# 01-POWER.net
KiCad netlist of a schematic drawn in Altium Designer
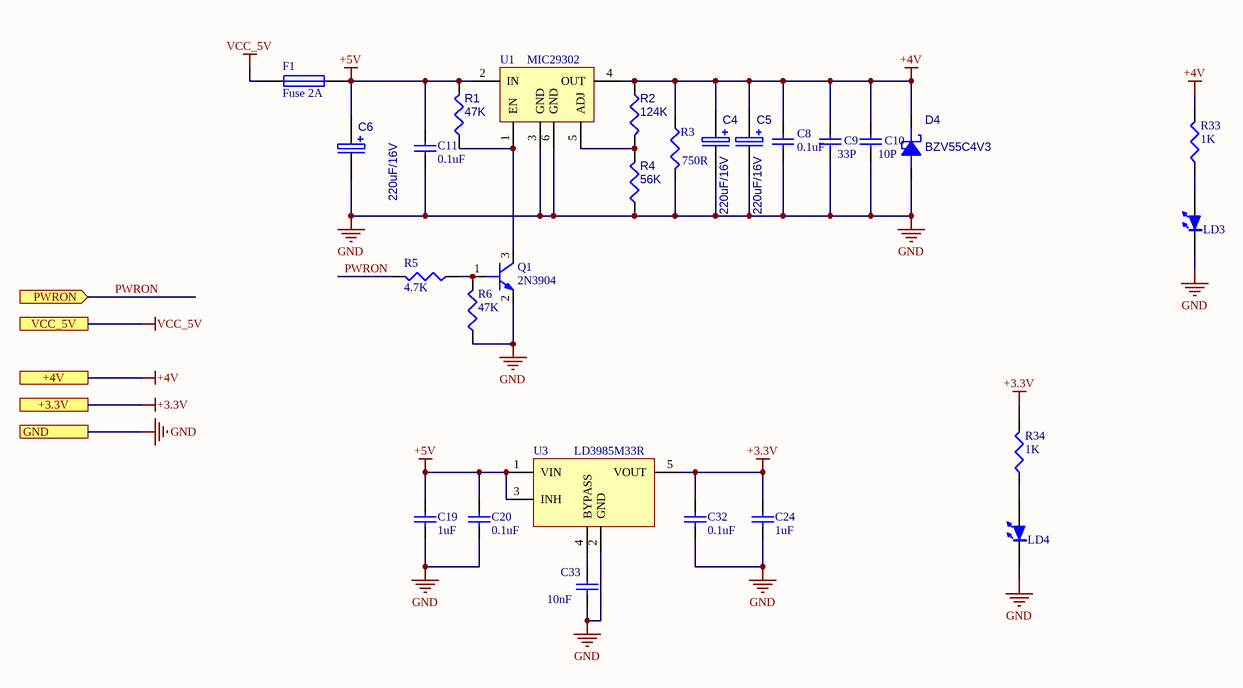
[diagram p0: 01-POWER.SchDoc]

(export (version "E")
  (design (tool "Eeschema 10.0.6"))
  (components
    (comp (ref "C4")
      (value "220uF/16V")
      (footprint "C_TAN_D")
      (description "E-CAP")
      (libsource (lib "*") (part "ECAP"))
    )
    (comp (ref "C5")
      (value "220uF/16V")
      (footprint "C_TAN_D")
      (description "E-CAP")
      (libsource (lib "*") (part "ECAP"))
    )
    (comp (ref "C6")
      (value "220uF/16V")
      (footprint "C_TAN_D")
      (description "E-CAP")
      (libsource (lib "*") (part "ECAP"))
    )
    (comp (ref "C8")
      (value "0.1uF")
      (footprint "0603_C")
      (description "Capacitor")
      (fields (field (name "PUBLISHER") "Altium Limited"))
      (libsource (lib "EP_MCB_V3.00") (part "Cap Semi"))
    )
    (comp (ref "C9")
      (value "33P")
      (footprint "0603_C")
      (description "Capacitor")
      (fields (field (name "PUBLISHER") "Altium Limited"))
      (libsource (lib "EP_MCB_V3.00") (part "Cap Semi"))
    )
    (comp (ref "C10")
      (value "10P")
      (footprint "0603_C")
      (description "Capacitor")
      (fields (field (name "PUBLISHER") "Altium Limited"))
      (libsource (lib "EP_MCB_V3.00") (part "Cap Semi"))
    )
    (comp (ref "C11")
      (value "0.1uF")
      (footprint "0603_C")
      (description "Capacitor")
      (fields (field (name "PUBLISHER") "Altium Limited"))
      (libsource (lib "EP_MCB_V3.00") (part "Cap Semi"))
    )
    (comp (ref "C19")
      (value "1uF")
      (footprint "0603_C")
      (description "Capacitor")
      (fields (field (name "PUBLISHER") "Altium Limited"))
      (libsource (lib "EM_SENSOR_V3.01") (part "Cap Semi_1"))
    )
    (comp (ref "C20")
      (value "0.1uF")
      (footprint "0603_C")
      (description "Capacitor")
      (fields (field (name "PUBLISHER") "Altium Limited"))
      (libsource (lib "EM_SENSOR_V3.01") (part "Cap Semi_1"))
    )
    (comp (ref "C24")
      (value "1uF")
      (footprint "0603_C")
      (description "Capacitor")
      (fields (field (name "PUBLISHER") "Altium Limited"))
      (libsource (lib "EM_SENSOR_V3.01") (part "Cap Semi_1"))
    )
    (comp (ref "C32")
      (value "0.1uF")
      (footprint "0603_C")
      (description "Capacitor")
      (fields (field (name "PUBLISHER") "Altium Limited"))
      (libsource (lib "EM_SENSOR_V3.01") (part "Cap Semi_1"))
    )
    (comp (ref "C33")
      (value "10nF")
      (footprint "0603_C")
      (description "Capacitor")
      (fields (field (name "PUBLISHER") "Altium Limited"))
      (libsource (lib "EM_SENSOR_V3.01") (part "Cap Semi_1"))
    )
    (comp (ref "D4")
      (value "BZV55C4V3")
      (footprint "SOD-80")
      (libsource (lib "EP_MCB_V4.1") (part "DIODE SCHOTTKY"))
    )
    (comp (ref "F1")
      (value "Fuse 2A")
      (footprint "1812_F")
      (description "Fuse")
      (fields (field (name "PUBLISHER") "Altium Limited"))
      (libsource (lib "Miscellaneous Devices") (part "Fuse 1"))
    )
    (comp (ref "LD3")
      (value "WHITE")
      (footprint "LED_0603")
      (description "LED")
      (libsource (lib "*") (part "LED"))
    )
    (comp (ref "LD4")
      (value "WHITE")
      (footprint "LED_0603")
      (description "LED")
      (libsource (lib "*") (part "LED"))
    )
    (comp (ref "Q1") (value "2N3904") (footprint "SOT23") (libsource (lib "MySchlib") (part "NPN")))
    (comp (ref "R1")
      (value "47K")
      (footprint "0603_R")
      (description "RESISTOR")
      (libsource (lib "*") (part "R0.25W"))
    )
    (comp (ref "R2")
      (value "124K")
      (footprint "0603_R")
      (description "RESISTOR")
      (libsource (lib "*") (part "R0.25W"))
    )
    (comp (ref "R3") (value "750R") (footprint "0603_R") (libsource (lib "") (part "RES1_1")))
    (comp (ref "R4")
      (value "56K")
      (footprint "0603_R")
      (description "RESISTOR")
      (libsource (lib "*") (part "R0.25W"))
    )
    (comp (ref "R5") (value "4.7K") (footprint "0603_R") (libsource (lib "MySchlib") (part "RES1")))
    (comp (ref "R6") (value "47K") (footprint "0603_R") (libsource (lib "MySchlib") (part "RES1")))
    (comp (ref "R33") (value "1K") (footprint "0603_R") (libsource (lib "MySchlib") (part "RES1")))
    (comp (ref "R34") (value "1K") (footprint "0603_R") (libsource (lib "MySchlib") (part "RES1")))
    (comp (ref "U1") (value "MIC29302") (footprint "TO-263-5") (libsource (lib "MySchlib") (part "MIC29302")))
    (comp (ref "U3")
      (value "LD3985M33R")
      (footprint "SOT23-5L")
      (libsource (lib "MySchlib") (part "LD3985MSSR"))
    )
  )
  (nets
    (net (code "1") (name "+3.3V") (class "Default")
      (node (ref "C24") (pin "1") (pinfunction "1_1") (pintype "passive"))
      (node (ref "C32") (pin "1") (pinfunction "1_1") (pintype "passive"))
      (node (ref "R34") (pin "1") (pinfunction "1_1") (pintype "passive"))
      (node (ref "U3") (pin "5") (pinfunction "VOUT_5") (pintype "passive"))
    )
    (net (code "2") (name "+4V") (class "Default")
      (node (ref "C10") (pin "2") (pinfunction "2_2") (pintype "passive"))
      (node (ref "C4") (pin "1") (pinfunction "+_1") (pintype "passive"))
      (node (ref "C5") (pin "1") (pinfunction "+_1") (pintype "passive"))
      (node (ref "C8") (pin "2") (pinfunction "2_2") (pintype "passive"))
      (node (ref "C9") (pin "2") (pinfunction "2_2") (pintype "passive"))
      (node (ref "D4") (pin "2") (pinfunction "CATHODE_2") (pintype "passive"))
      (node (ref "R2") (pin "2") (pinfunction "2_2") (pintype "passive"))
      (node (ref "R3") (pin "2") (pinfunction "2_2") (pintype "passive"))
      (node (ref "R33") (pin "1") (pinfunction "1_1") (pintype "passive"))
      (node (ref "U1") (pin "4") (pinfunction "OUT_4") (pintype "passive"))
    )
    (net (code "3") (name "+5V") (class "Default")
      (node (ref "C11") (pin "2") (pinfunction "2_2") (pintype "passive"))
      (node (ref "C19") (pin "1") (pinfunction "1_1") (pintype "passive"))
      (node (ref "C20") (pin "1") (pinfunction "1_1") (pintype "passive"))
      (node (ref "C6") (pin "1") (pinfunction "+_1") (pintype "passive"))
      (node (ref "F1") (pin "2") (pinfunction "2_2") (pintype "passive"))
      (node (ref "R1") (pin "1") (pinfunction "1_1") (pintype "passive"))
      (node (ref "U1") (pin "2") (pinfunction "IN_2") (pintype "passive"))
      (node (ref "U3") (pin "1") (pinfunction "VIN_1") (pintype "passive"))
      (node (ref "U3") (pin "3") (pinfunction "INH_3") (pintype "passive"))
    )
    (net (code "4") (name "/PWRON") (class "Default")
      (node (ref "R5") (pin "1") (pinfunction "1_1") (pintype "passive"))
    )
    (net (code "5") (name "GND") (class "Default")
      (node (ref "C10") (pin "1") (pinfunction "1_1") (pintype "passive"))
      (node (ref "C11") (pin "1") (pinfunction "1_1") (pintype "passive"))
      (node (ref "C19") (pin "2") (pinfunction "2_2") (pintype "passive"))
      (node (ref "C20") (pin "2") (pinfunction "2_2") (pintype "passive"))
      (node (ref "C24") (pin "2") (pinfunction "2_2") (pintype "passive"))
      (node (ref "C32") (pin "2") (pinfunction "2_2") (pintype "passive"))
      (node (ref "C33") (pin "2") (pinfunction "2_2") (pintype "passive"))
      (node (ref "C4") (pin "2") (pinfunction "-_2") (pintype "passive"))
      (node (ref "C5") (pin "2") (pinfunction "-_2") (pintype "passive"))
      (node (ref "C6") (pin "2") (pinfunction "-_2") (pintype "passive"))
      (node (ref "C8") (pin "1") (pinfunction "1_1") (pintype "passive"))
      (node (ref "C9") (pin "1") (pinfunction "1_1") (pintype "passive"))
      (node (ref "D4") (pin "1") (pinfunction "ANODE_1") (pintype "passive"))
      (node (ref "LD3") (pin "K") (pinfunction "K_K") (pintype "passive"))
      (node (ref "LD4") (pin "K") (pinfunction "K_K") (pintype "passive"))
      (node (ref "Q1") (pin "2") (pinfunction "EMITTER_2") (pintype "passive"))
      (node (ref "R3") (pin "1") (pinfunction "1_1") (pintype "passive"))
      (node (ref "R4") (pin "2") (pinfunction "2_2") (pintype "passive"))
      (node (ref "R6") (pin "2") (pinfunction "2_2") (pintype "passive"))
      (node (ref "U1") (pin "3") (pinfunction "GND_3") (pintype "passive"))
      (node (ref "U1") (pin "6") (pinfunction "GND_6") (pintype "passive"))
      (node (ref "U3") (pin "2") (pinfunction "GND_2") (pintype "passive"))
    )
    (net (code "6") (name "Net-(LD3-PadA)") (class "Default")
      (node (ref "LD3") (pin "A") (pinfunction "A_A") (pintype "passive"))
      (node (ref "R33") (pin "2") (pinfunction "2_2") (pintype "passive"))
    )
    (net (code "7") (name "Net-(LD4-PadA)") (class "Default")
      (node (ref "LD4") (pin "A") (pinfunction "A_A") (pintype "passive"))
      (node (ref "R34") (pin "2") (pinfunction "2_2") (pintype "passive"))
    )
    (net (code "8") (name "Net-(Q1-BASE)") (class "Default")
      (node (ref "Q1") (pin "1") (pinfunction "BASE_1") (pintype "passive"))
      (node (ref "R5") (pin "2") (pinfunction "2_2") (pintype "passive"))
      (node (ref "R6") (pin "1") (pinfunction "1_1") (pintype "passive"))
    )
    (net (code "9") (name "Net-(Q1-COLLECTOR)") (class "Default")
      (node (ref "Q1") (pin "3") (pinfunction "COLLECTOR_3") (pintype "passive"))
      (node (ref "R1") (pin "2") (pinfunction "2_2") (pintype "passive"))
      (node (ref "U1") (pin "1") (pinfunction "EN_1") (pintype "passive"))
    )
    (net (code "10") (name "Net-(U1-ADJ)") (class "Default")
      (node (ref "R2") (pin "1") (pinfunction "1_1") (pintype "passive"))
      (node (ref "R4") (pin "1") (pinfunction "1_1") (pintype "passive"))
      (node (ref "U1") (pin "5") (pinfunction "ADJ_5") (pintype "passive"))
    )
    (net (code "11") (name "Net-(U3-BYPASS)") (class "Default")
      (node (ref "C33") (pin "1") (pinfunction "1_1") (pintype "passive"))
      (node (ref "U3") (pin "4") (pinfunction "BYPASS_4") (pintype "passive"))
    )
    (net (code "12") (name "VCC_5V") (class "Default")
      (node (ref "F1") (pin "1") (pinfunction "1_1") (pintype "passive"))
    )
  )
)
